# eEvo_v1_7_MP8770.net
KiCad netlist of a schematic drawn in EAGLE
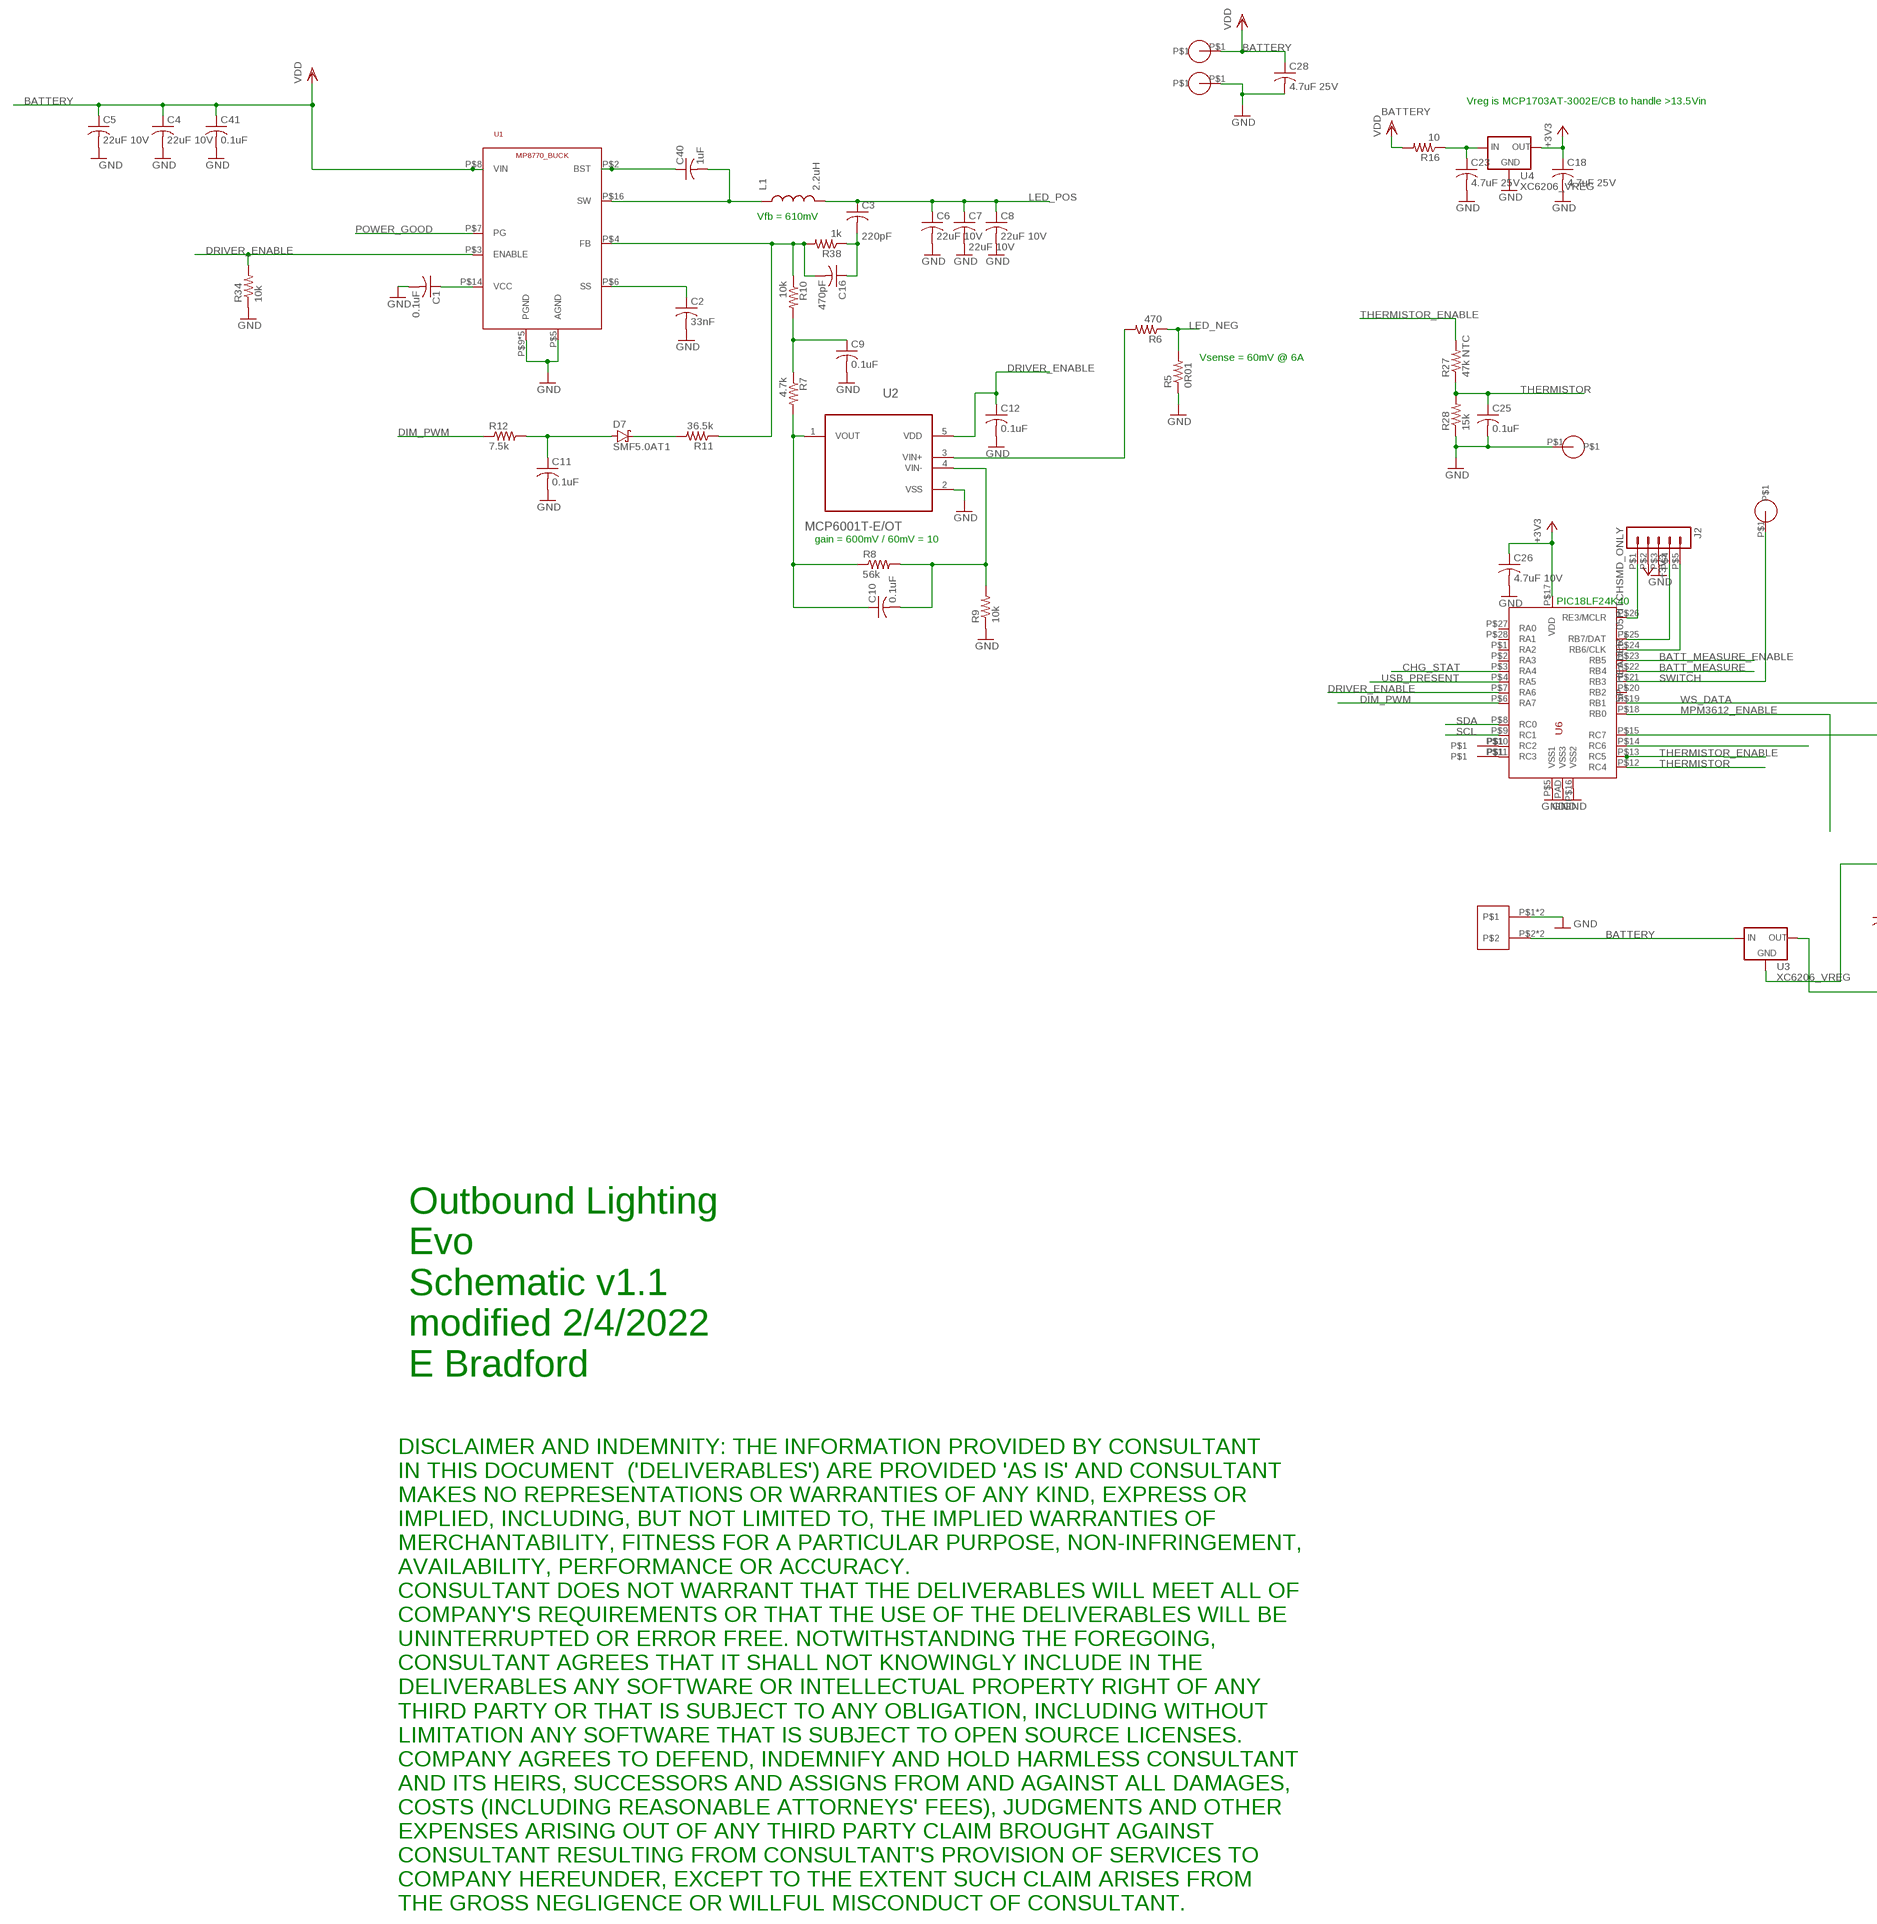
[diagram p0: schematic, sheet 1, part 1 of 2]
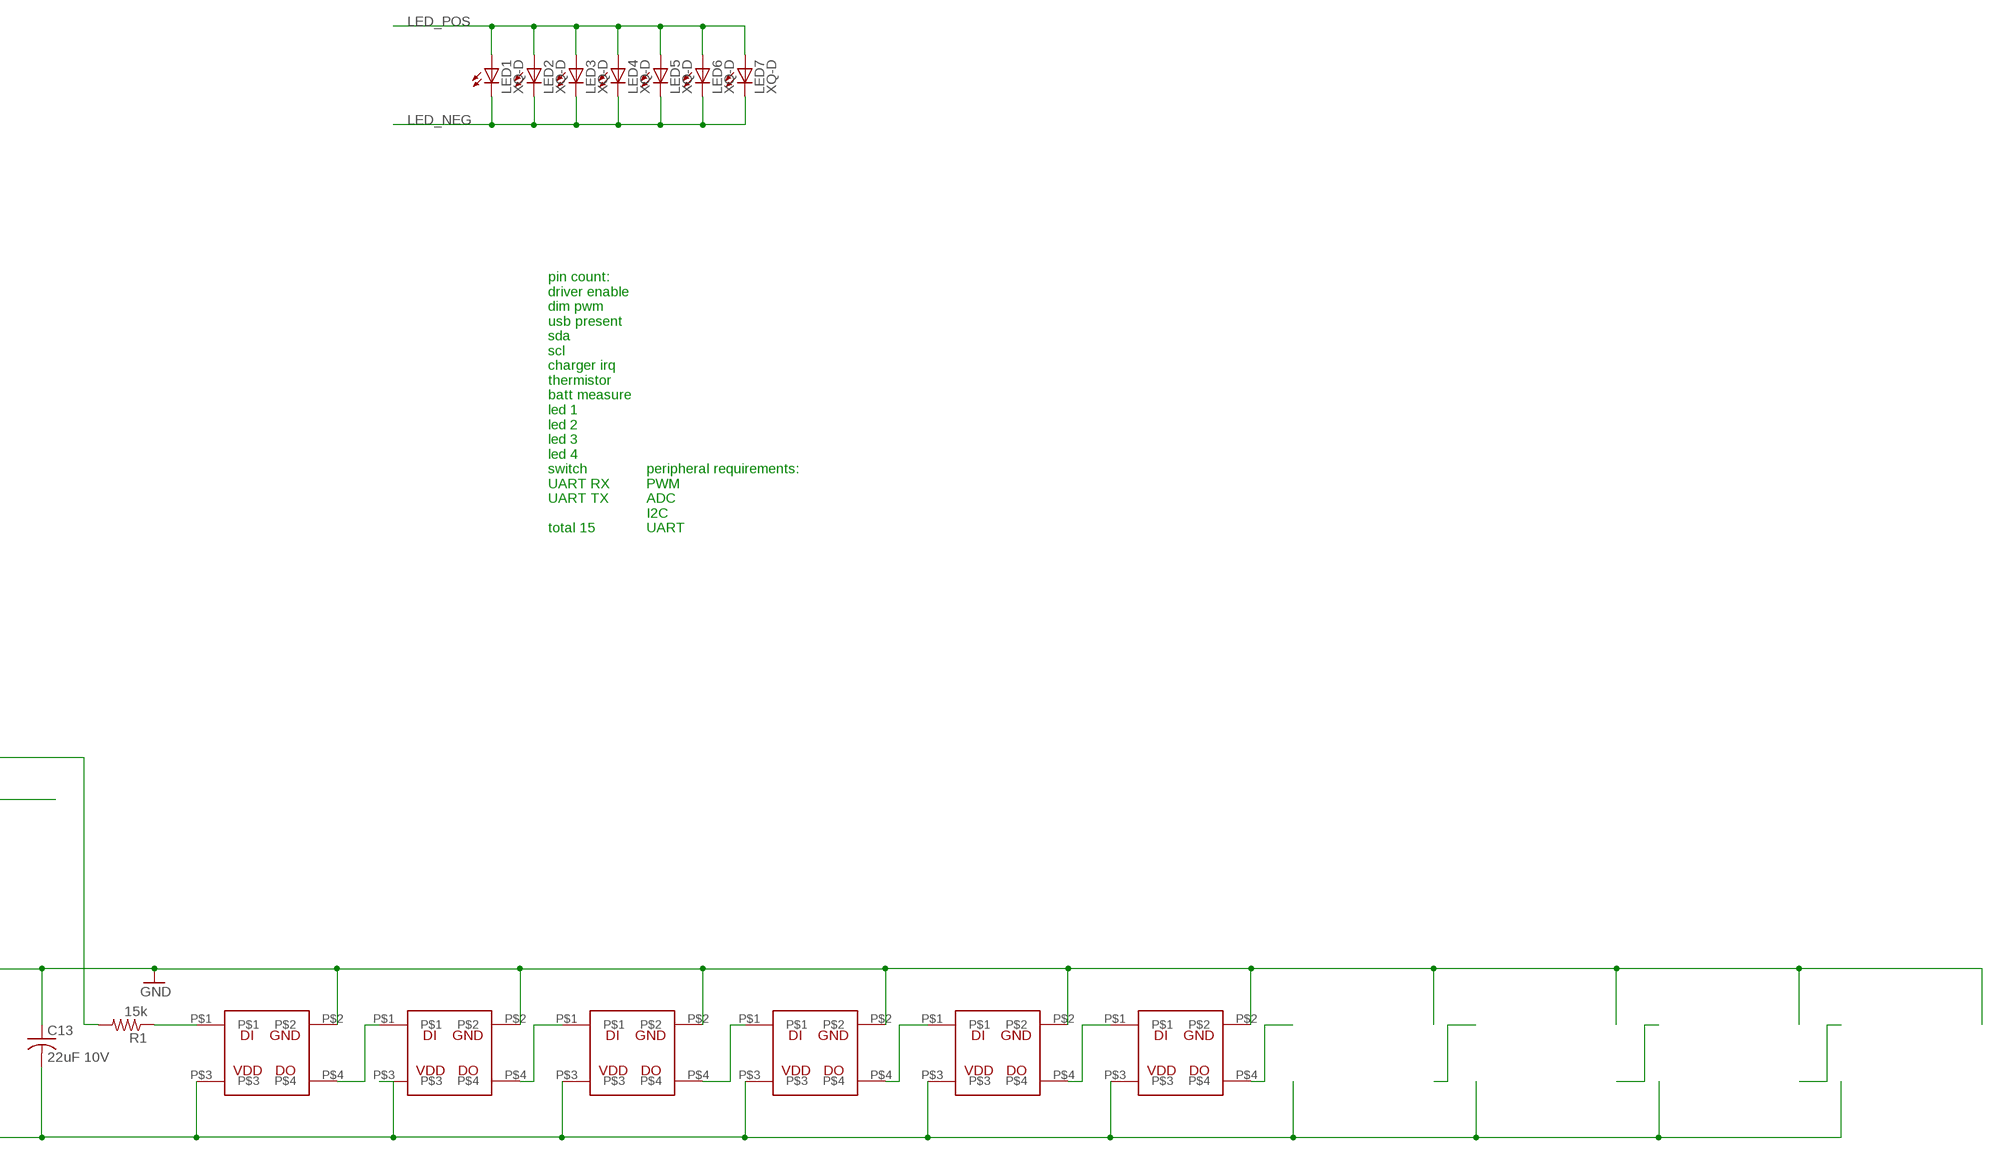
[diagram p1: schematic, sheet 1, part 2 of 2]

(export (version "E")
  (design (tool "Eeschema 10.0.6"))
  (components
    (comp (ref "C1")
      (value "0.1uF")
      (footprint "eagle-import:C0603")
      (libsource (lib "eagle-import") (part "C-USC0603"))
    )
    (comp (ref "C2")
      (value "33nF")
      (footprint "eagle-import:C0603")
      (libsource (lib "eagle-import") (part "C-USC0603"))
    )
    (comp (ref "C3")
      (value "220pF")
      (footprint "eagle-import:C0603")
      (libsource (lib "eagle-import") (part "C-USC0603"))
    )
    (comp (ref "C4")
      (value "22uF 10V")
      (footprint "eagle-import:C0603")
      (libsource (lib "eagle-import") (part "C-USC0603"))
    )
    (comp (ref "C5")
      (value "22uF 10V")
      (footprint "eagle-import:C0603")
      (libsource (lib "eagle-import") (part "C-USC0603"))
    )
    (comp (ref "C6")
      (value "22uF 10V")
      (footprint "eagle-import:C0603")
      (libsource (lib "eagle-import") (part "C-USC0603"))
    )
    (comp (ref "C7")
      (value "22uF 10V")
      (footprint "eagle-import:C0603")
      (libsource (lib "eagle-import") (part "C-USC0603"))
    )
    (comp (ref "C8")
      (value "22uF 10V")
      (footprint "eagle-import:C0603")
      (libsource (lib "eagle-import") (part "C-USC0603"))
    )
    (comp (ref "C9")
      (value "0.1uF")
      (footprint "eagle-import:C0603")
      (libsource (lib "eagle-import") (part "C-USC0603"))
    )
    (comp (ref "C10")
      (value "0.1uF")
      (footprint "eagle-import:C0603")
      (libsource (lib "eagle-import") (part "C-USC0603"))
    )
    (comp (ref "C11")
      (value "0.1uF")
      (footprint "eagle-import:C0603")
      (libsource (lib "eagle-import") (part "C-USC0603"))
    )
    (comp (ref "C12")
      (value "0.1uF")
      (footprint "eagle-import:C0603")
      (libsource (lib "eagle-import") (part "C-USC0603"))
    )
    (comp (ref "C13")
      (value "22uF 10V")
      (footprint "eagle-import:C0603")
      (libsource (lib "eagle-import") (part "C-USC0603"))
    )
    (comp (ref "C16")
      (value "470pF")
      (footprint "eagle-import:C0603")
      (libsource (lib "eagle-import") (part "C-USC0603"))
    )
    (comp (ref "C18")
      (value "4.7uF 25V")
      (footprint "eagle-import:C0603")
      (libsource (lib "eagle-import") (part "C-USC0603"))
    )
    (comp (ref "C23")
      (value "4.7uF 25V")
      (footprint "eagle-import:C0603")
      (libsource (lib "eagle-import") (part "C-USC0603"))
    )
    (comp (ref "C25")
      (value "0.1uF")
      (footprint "eagle-import:C0603")
      (libsource (lib "eagle-import") (part "C-USC0603"))
    )
    (comp (ref "C26")
      (value "4.7uF 10V")
      (footprint "eagle-import:C0603")
      (libsource (lib "eagle-import") (part "C-USC0603"))
    )
    (comp (ref "C28")
      (value "4.7uF 25V")
      (footprint "eagle-import:C0603")
      (libsource (lib "eagle-import") (part "C-USC0603"))
    )
    (comp (ref "C40")
      (value "1uF")
      (footprint "eagle-import:C0603")
      (libsource (lib "eagle-import") (part "C-USC0603"))
    )
    (comp (ref "C41")
      (value "0.1uF")
      (footprint "eagle-import:C0603")
      (libsource (lib "eagle-import") (part "C-USC0603"))
    )
    (comp (ref "D7")
      (value "SMF5.0AT1")
      (footprint "eagle-import:SOD123FL")
      (libsource (lib "eagle-import") (part "SMF5.0AT1"))
    )
    (comp (ref "J1")
      (value "CONN_2-PIN_MOLEX_PICOEZMATE")
      (footprint "eagle-import:CONN_2-PIN_MOLEX_PICOEZMATE")
      (libsource (lib "eagle-import") (part "CONN_2-PIN_MOLEX_PICOEZMATE"))
    )
    (comp (ref "J2")
      (value "5P_HEADER_.05PITCHSMD_ONLY")
      (footprint "eagle-import:5P_ICSP_SMD")
      (libsource (lib "eagle-import") (part "5P_HEADER_.05PITCHSMD_ONLY"))
    )
    (comp (ref "L1")
      (value "2.2uH")
      (footprint "eagle-import:INDUCTOR_5.7X5.2")
      (libsource (lib "eagle-import") (part "SMD_INDUCT_5.7X5.2"))
    )
    (comp (ref "LED1")
      (value "XQ-D")
      (footprint "eagle-import:XQ-D")
      (libsource (lib "eagle-import") (part "XQ-D"))
    )
    (comp (ref "LED2")
      (value "XQ-D")
      (footprint "eagle-import:XQ-D")
      (libsource (lib "eagle-import") (part "XQ-D"))
    )
    (comp (ref "LED3")
      (value "XQ-D")
      (footprint "eagle-import:XQ-D")
      (libsource (lib "eagle-import") (part "XQ-D"))
    )
    (comp (ref "LED4")
      (value "XQ-D")
      (footprint "eagle-import:XQ-D")
      (libsource (lib "eagle-import") (part "XQ-D"))
    )
    (comp (ref "LED5")
      (value "XQ-D")
      (footprint "eagle-import:XQ-D")
      (libsource (lib "eagle-import") (part "XQ-D"))
    )
    (comp (ref "LED6")
      (value "XQ-D")
      (footprint "eagle-import:XQ-D")
      (libsource (lib "eagle-import") (part "XQ-D"))
    )
    (comp (ref "LED7")
      (value "XQ-D")
      (footprint "eagle-import:XQ-D")
      (libsource (lib "eagle-import") (part "XQ-D"))
    )
    (comp (ref "R1")
      (value "15k")
      (footprint "eagle-import:R0603")
      (libsource (lib "eagle-import") (part "R-US_R0603"))
    )
    (comp (ref "R5")
      (value "0R01")
      (footprint "eagle-import:M1206")
      (libsource (lib "eagle-import") (part "R-US_M1206"))
    )
    (comp (ref "R6")
      (value "470")
      (footprint "eagle-import:R0603")
      (libsource (lib "eagle-import") (part "R-US_R0603"))
    )
    (comp (ref "R7")
      (value "4.7k")
      (footprint "eagle-import:R0603")
      (libsource (lib "eagle-import") (part "R-US_R0603"))
    )
    (comp (ref "R8")
      (value "56k")
      (footprint "eagle-import:R0603")
      (libsource (lib "eagle-import") (part "R-US_R0603"))
    )
    (comp (ref "R9")
      (value "10k")
      (footprint "eagle-import:R0603")
      (libsource (lib "eagle-import") (part "R-US_R0603"))
    )
    (comp (ref "R10")
      (value "10k")
      (footprint "eagle-import:R0603")
      (libsource (lib "eagle-import") (part "R-US_R0603"))
    )
    (comp (ref "R11")
      (value "36.5k")
      (footprint "eagle-import:R0603")
      (libsource (lib "eagle-import") (part "R-US_R0603"))
    )
    (comp (ref "R12")
      (value "7.5k")
      (footprint "eagle-import:R0603")
      (libsource (lib "eagle-import") (part "R-US_R0603"))
    )
    (comp (ref "R16")
      (value "10")
      (footprint "eagle-import:R0603")
      (libsource (lib "eagle-import") (part "R-US_R0603"))
    )
    (comp (ref "R27")
      (value "47k NTC")
      (footprint "eagle-import:R0603")
      (libsource (lib "eagle-import") (part "R-US_R0603"))
    )
    (comp (ref "R28")
      (value "15k")
      (footprint "eagle-import:R0603")
      (libsource (lib "eagle-import") (part "R-US_R0603"))
    )
    (comp (ref "R34")
      (value "10k")
      (footprint "eagle-import:R0603")
      (libsource (lib "eagle-import") (part "R-US_R0603"))
    )
    (comp (ref "R38")
      (value "1k")
      (footprint "eagle-import:R0603")
      (libsource (lib "eagle-import") (part "R-US_R0603"))
    )
    (comp (ref "RX")
      (value "WIREPAD_50MIL")
      (footprint "eagle-import:WIREPAD_50MIL")
      (libsource (lib "eagle-import") (part "WIREPAD_50MIL"))
    )
    (comp (ref "TX")
      (value "WIREPAD_50MIL")
      (footprint "eagle-import:WIREPAD_50MIL")
      (libsource (lib "eagle-import") (part "WIREPAD_50MIL"))
    )
    (comp (ref "U$2")
      (value "WS2812B-2020")
      (footprint "eagle-import:WS2812B-2020")
      (libsource (lib "eagle-import") (part "WS2812B-2020"))
    )
    (comp (ref "U$3")
      (value "WS2812B-2020")
      (footprint "eagle-import:WS2812B-2020")
      (libsource (lib "eagle-import") (part "WS2812B-2020"))
    )
    (comp (ref "U$4")
      (value "WS2812B-2020")
      (footprint "eagle-import:WS2812B-2020")
      (libsource (lib "eagle-import") (part "WS2812B-2020"))
    )
    (comp (ref "U$5")
      (value "WS2812B-2020")
      (footprint "eagle-import:WS2812B-2020")
      (libsource (lib "eagle-import") (part "WS2812B-2020"))
    )
    (comp (ref "U$6")
      (value "WS2812B-2020")
      (footprint "eagle-import:WS2812B-2020")
      (libsource (lib "eagle-import") (part "WS2812B-2020"))
    )
    (comp (ref "U$7")
      (value "WS2812B-2020")
      (footprint "eagle-import:WS2812B-2020")
      (libsource (lib "eagle-import") (part "WS2812B-2020"))
    )
    (comp (ref "U$12")
      (value "WIREPAD2X2MM_SQ")
      (footprint "eagle-import:PAD_2X2")
      (libsource (lib "eagle-import") (part "WIREPAD2X2MM_SQ"))
    )
    (comp (ref "U$13")
      (value "WIREPAD2X2MM_SQ")
      (footprint "eagle-import:PAD_2X2")
      (libsource (lib "eagle-import") (part "WIREPAD2X2MM_SQ"))
    )
    (comp (ref "U$14")
      (value "WIREPAD2X2MM_SQ")
      (footprint "eagle-import:PAD_2X2")
      (libsource (lib "eagle-import") (part "WIREPAD2X2MM_SQ"))
    )
    (comp (ref "U$15")
      (value "WIREPAD2X2MM_SQ")
      (footprint "eagle-import:PAD_2X2")
      (libsource (lib "eagle-import") (part "WIREPAD2X2MM_SQ"))
    )
    (comp (ref "U1")
      (value "MP8770_BUCK")
      (footprint "eagle-import:MP8770_BUCK")
      (libsource (lib "eagle-import") (part "MP8770_BUCK"))
    )
    (comp (ref "U2")
      (value "MCP6001T-E/OT")
      (footprint "eagle-import:SOT95P270X145-5N")
      (libsource (lib "eagle-import") (part "MCP6001T-E/OT"))
    )
    (comp (ref "U3")
      (value "XC6206_VREG")
      (footprint "eagle-import:SOT-23")
      (libsource (lib "eagle-import") (part "XC6206_VREG"))
    )
    (comp (ref "U4")
      (value "XC6206_VREG")
      (footprint "eagle-import:SOT-23")
      (libsource (lib "eagle-import") (part "XC6206_VREG"))
    )
    (comp (ref "U6")
      (value "PIC18F25K40UQFN_4X4")
      (footprint "eagle-import:UQFN-28_4X4")
      (libsource (lib "eagle-import") (part "PIC18F26K40UQFN_4X4"))
    )
  )
  (nets
    (net (code "1") (name "+3V3") (class "Default")
      (node (ref "C18") (pin "1") (pinfunction "1_1") (pintype "passive"))
      (node (ref "C26") (pin "1") (pinfunction "1_1") (pintype "passive"))
      (node (ref "J2") (pin "P$2") (pinfunction "2_P$2") (pintype "passive"))
      (node (ref "U4") (pin "2") (pinfunction "OUT_2") (pintype "passive"))
      (node (ref "U6") (pin "P$17") (pinfunction "VDD_P$17") (pintype "bidirectional"))
    )
    (net (code "2") (name "/BATT_MEASURE") (class "Default")
      (node (ref "U6") (pin "P$22") (pinfunction "RB4_P$22") (pintype "bidirectional"))
    )
    (net (code "3") (name "/BATT_MEASURE_ENABLE") (class "Default")
      (node (ref "U6") (pin "P$23") (pinfunction "RB5_P$23") (pintype "bidirectional"))
    )
    (net (code "4") (name "/CHG_STAT") (class "Default")
      (node (ref "U6") (pin "P$3") (pinfunction "RA4_P$3") (pintype "bidirectional"))
    )
    (net (code "5") (name "/DIM_PWM") (class "Default")
      (node (ref "R12") (pin "1") (pinfunction "1_1") (pintype "passive"))
      (node (ref "U6") (pin "P$6") (pinfunction "RA7_P$6") (pintype "bidirectional"))
    )
    (net (code "6") (name "/DRIVER_ENABLE") (class "Default")
      (node (ref "C12") (pin "1") (pinfunction "1_1") (pintype "passive"))
      (node (ref "R34") (pin "2") (pinfunction "2_2") (pintype "passive"))
      (node (ref "U1") (pin "P$3") (pinfunction "ENABLE_P$3") (pintype "bidirectional"))
      (node (ref "U2") (pin "5") (pinfunction "VDD_5") (pintype "power_in"))
      (node (ref "U6") (pin "P$7") (pinfunction "RA6_P$7") (pintype "bidirectional"))
    )
    (net (code "7") (name "/LED_NEG") (class "Default")
      (node (ref "LED1") (pin "2") (pinfunction "C_2") (pintype "passive"))
      (node (ref "LED2") (pin "2") (pinfunction "C_2") (pintype "passive"))
      (node (ref "LED3") (pin "2") (pinfunction "C_2") (pintype "passive"))
      (node (ref "LED4") (pin "2") (pinfunction "C_2") (pintype "passive"))
      (node (ref "LED5") (pin "2") (pinfunction "C_2") (pintype "passive"))
      (node (ref "LED6") (pin "2") (pinfunction "C_2") (pintype "passive"))
      (node (ref "LED7") (pin "2") (pinfunction "C_2") (pintype "passive"))
      (node (ref "R5") (pin "2") (pinfunction "2_2") (pintype "passive"))
      (node (ref "R6") (pin "1") (pinfunction "1_1") (pintype "passive"))
    )
    (net (code "8") (name "/LED_POS") (class "Default")
      (node (ref "C3") (pin "1") (pinfunction "1_1") (pintype "passive"))
      (node (ref "C6") (pin "1") (pinfunction "1_1") (pintype "passive"))
      (node (ref "C7") (pin "1") (pinfunction "1_1") (pintype "passive"))
      (node (ref "C8") (pin "1") (pinfunction "1_1") (pintype "passive"))
      (node (ref "L1") (pin "P$2") (pinfunction "2_P$2") (pintype "passive"))
      (node (ref "LED1") (pin "1") (pinfunction "A_1") (pintype "passive"))
      (node (ref "LED2") (pin "1") (pinfunction "A_1") (pintype "passive"))
      (node (ref "LED3") (pin "1") (pinfunction "A_1") (pintype "passive"))
      (node (ref "LED4") (pin "1") (pinfunction "A_1") (pintype "passive"))
      (node (ref "LED5") (pin "1") (pinfunction "A_1") (pintype "passive"))
      (node (ref "LED6") (pin "1") (pinfunction "A_1") (pintype "passive"))
      (node (ref "LED7") (pin "1") (pinfunction "A_1") (pintype "passive"))
    )
    (net (code "9") (name "/MPM3612_ENABLE") (class "Default")
      (node (ref "U6") (pin "P$18") (pinfunction "RB0_P$18") (pintype "bidirectional"))
    )
    (net (code "10") (name "/POWER_GOOD") (class "Default")
      (node (ref "U1") (pin "P$7") (pinfunction "PG_P$7") (pintype "bidirectional"))
    )
    (net (code "11") (name "/SCL") (class "Default")
      (node (ref "U6") (pin "P$9") (pinfunction "RC1_P$9") (pintype "bidirectional"))
    )
    (net (code "12") (name "/SDA") (class "Default")
      (node (ref "U6") (pin "P$8") (pinfunction "RC0_P$8") (pintype "bidirectional"))
    )
    (net (code "13") (name "/SWITCH") (class "Default")
      (node (ref "U$12") (pin "P$1") (pinfunction "P$1_P$1") (pintype "bidirectional"))
      (node (ref "U6") (pin "P$21") (pinfunction "RB3_P$21") (pintype "bidirectional"))
    )
    (net (code "14") (name "/THERMISTOR") (class "Default")
      (node (ref "C25") (pin "1") (pinfunction "1_1") (pintype "passive"))
      (node (ref "R27") (pin "1") (pinfunction "1_1") (pintype "passive"))
      (node (ref "R28") (pin "2") (pinfunction "2_2") (pintype "passive"))
      (node (ref "U6") (pin "P$12") (pinfunction "RC4_P$12") (pintype "bidirectional"))
    )
    (net (code "15") (name "/THERMISTOR_ENABLE") (class "Default")
      (node (ref "R27") (pin "2") (pinfunction "2_2") (pintype "passive"))
      (node (ref "U6") (pin "P$13") (pinfunction "RC5_P$13") (pintype "bidirectional"))
    )
    (net (code "16") (name "/USB_PRESENT") (class "Default")
      (node (ref "U6") (pin "P$4") (pinfunction "RA5_P$4") (pintype "bidirectional"))
    )
    (net (code "17") (name "/WS_DATA") (class "Default")
      (node (ref "R1") (pin "2") (pinfunction "2_2") (pintype "passive"))
      (node (ref "U6") (pin "P$19") (pinfunction "RB1_P$19") (pintype "bidirectional"))
    )
    (net (code "18") (name "GND") (class "Default")
      (node (ref "C1") (pin "2") (pinfunction "2_2") (pintype "passive"))
      (node (ref "C11") (pin "2") (pinfunction "2_2") (pintype "passive"))
      (node (ref "C12") (pin "2") (pinfunction "2_2") (pintype "passive"))
      (node (ref "C13") (pin "1") (pinfunction "1_1") (pintype "passive"))
      (node (ref "C18") (pin "2") (pinfunction "2_2") (pintype "passive"))
      (node (ref "C2") (pin "2") (pinfunction "2_2") (pintype "passive"))
      (node (ref "C23") (pin "2") (pinfunction "2_2") (pintype "passive"))
      (node (ref "C25") (pin "2") (pinfunction "2_2") (pintype "passive"))
      (node (ref "C26") (pin "2") (pinfunction "2_2") (pintype "passive"))
      (node (ref "C28") (pin "2") (pinfunction "2_2") (pintype "passive"))
      (node (ref "C4") (pin "2") (pinfunction "2_2") (pintype "passive"))
      (node (ref "C41") (pin "2") (pinfunction "2_2") (pintype "passive"))
      (node (ref "C5") (pin "2") (pinfunction "2_2") (pintype "passive"))
      (node (ref "C6") (pin "2") (pinfunction "2_2") (pintype "passive"))
      (node (ref "C7") (pin "2") (pinfunction "2_2") (pintype "passive"))
      (node (ref "C8") (pin "2") (pinfunction "2_2") (pintype "passive"))
      (node (ref "C9") (pin "2") (pinfunction "2_2") (pintype "passive"))
      (node (ref "J1") (pin "P$1") (pinfunction "P$1_P$1") (pintype "bidirectional"))
      (node (ref "J1") (pin "P$4") (pinfunction "P$1_P$4") (pintype "bidirectional"))
      (node (ref "J2") (pin "P$3") (pinfunction "3_P$3") (pintype "passive"))
      (node (ref "R28") (pin "1") (pinfunction "1_1") (pintype "passive"))
      (node (ref "R34") (pin "1") (pinfunction "1_1") (pintype "passive"))
      (node (ref "R5") (pin "1") (pinfunction "1_1") (pintype "passive"))
      (node (ref "R9") (pin "1") (pinfunction "1_1") (pintype "passive"))
      (node (ref "U$13") (pin "P$1") (pinfunction "P$1_P$1") (pintype "bidirectional"))
      (node (ref "U$15") (pin "P$1") (pinfunction "P$1_P$1") (pintype "bidirectional"))
      (node (ref "U$2") (pin "P$2") (pinfunction "P$2_P$2") (pintype "bidirectional"))
      (node (ref "U$3") (pin "P$2") (pinfunction "P$2_P$2") (pintype "bidirectional"))
      (node (ref "U$4") (pin "P$2") (pinfunction "P$2_P$2") (pintype "bidirectional"))
      (node (ref "U$5") (pin "P$2") (pinfunction "P$2_P$2") (pintype "bidirectional"))
      (node (ref "U$6") (pin "P$2") (pinfunction "P$2_P$2") (pintype "bidirectional"))
      (node (ref "U$7") (pin "P$2") (pinfunction "P$2_P$2") (pintype "bidirectional"))
      (node (ref "U1") (pin "P$10") (pinfunction "PGND_P$10") (pintype "bidirectional"))
      (node (ref "U1") (pin "P$11") (pinfunction "PGND_P$11") (pintype "bidirectional"))
      (node (ref "U1") (pin "P$12") (pinfunction "PGND_P$12") (pintype "bidirectional"))
      (node (ref "U1") (pin "P$13") (pinfunction "PGND_P$13") (pintype "bidirectional"))
      (node (ref "U1") (pin "P$5") (pinfunction "AGND_P$5") (pintype "bidirectional"))
      (node (ref "U1") (pin "P$9") (pinfunction "PGND_P$9") (pintype "bidirectional"))
      (node (ref "U2") (pin "2") (pinfunction "VSS_2") (pintype "passive"))
      (node (ref "U3") (pin "1") (pinfunction "GND_1") (pintype "input"))
      (node (ref "U4") (pin "1") (pinfunction "GND_1") (pintype "input"))
      (node (ref "U6") (pin "P$16") (pinfunction "VSS2_P$16") (pintype "bidirectional"))
      (node (ref "U6") (pin "P$5") (pinfunction "VSS1_P$5") (pintype "bidirectional"))
      (node (ref "U6") (pin "PAD") (pinfunction "VSS3_PAD") (pintype "bidirectional"))
    )
    (net (code "19") (name "Net-(C9-Pad1)") (class "Default")
      (node (ref "C9") (pin "1") (pinfunction "1_1") (pintype "passive"))
      (node (ref "R10") (pin "2") (pinfunction "2_2") (pintype "passive"))
      (node (ref "R7") (pin "1") (pinfunction "1_1") (pintype "passive"))
    )
    (net (code "20") (name "Net-(C11-Pad1)") (class "Default")
      (node (ref "C11") (pin "1") (pinfunction "1_1") (pintype "passive"))
      (node (ref "D7") (pin "A") (pinfunction "A_A") (pintype "passive"))
      (node (ref "R12") (pin "2") (pinfunction "2_2") (pintype "passive"))
    )
    (net (code "21") (name "Net-(C16-Pad1)") (class "Default")
      (node (ref "C16") (pin "1") (pinfunction "1_1") (pintype "passive"))
      (node (ref "C3") (pin "2") (pinfunction "2_2") (pintype "passive"))
      (node (ref "R38") (pin "1") (pinfunction "1_1") (pintype "passive"))
    )
    (net (code "22") (name "Net-(D7-PadC)") (class "Default")
      (node (ref "D7") (pin "C") (pinfunction "C_C") (pintype "passive"))
      (node (ref "R11") (pin "2") (pinfunction "2_2") (pintype "passive"))
    )
    (net (code "23") (name "Net-(J2-1)") (class "Default")
      (node (ref "J2") (pin "P$1") (pinfunction "1_P$1") (pintype "passive"))
      (node (ref "U6") (pin "P$26") (pinfunction "RE3/MCLR_P$26") (pintype "bidirectional"))
    )
    (net (code "24") (name "Net-(J2-4)") (class "Default")
      (node (ref "J2") (pin "P$4") (pinfunction "4_P$4") (pintype "passive"))
      (node (ref "U6") (pin "P$25") (pinfunction "RB7/DAT_P$25") (pintype "bidirectional"))
    )
    (net (code "25") (name "Net-(J2-5)") (class "Default")
      (node (ref "J2") (pin "P$5") (pinfunction "5_P$5") (pintype "passive"))
      (node (ref "U6") (pin "P$24") (pinfunction "RB6/CLK_P$24") (pintype "bidirectional"))
    )
    (net (code "26") (name "Net-(L1-1)") (class "Default")
      (node (ref "C40") (pin "2") (pinfunction "2_2") (pintype "passive"))
      (node (ref "L1") (pin "P$1") (pinfunction "1_P$1") (pintype "passive"))
      (node (ref "U1") (pin "P$16") (pinfunction "SW_P$16") (pintype "bidirectional"))
    )
    (net (code "27") (name "Net-(R1-Pad1)") (class "Default")
      (node (ref "R1") (pin "1") (pinfunction "1_1") (pintype "passive"))
      (node (ref "U$2") (pin "P$1") (pinfunction "P$1_P$1") (pintype "bidirectional"))
    )
    (net (code "28") (name "Net-(U$2-PadP$4)") (class "Default")
      (node (ref "U$2") (pin "P$4") (pinfunction "P$4_P$4") (pintype "bidirectional"))
      (node (ref "U$3") (pin "P$1") (pinfunction "P$1_P$1") (pintype "bidirectional"))
    )
    (net (code "29") (name "Net-(U$3-PadP$4)") (class "Default")
      (node (ref "U$3") (pin "P$4") (pinfunction "P$4_P$4") (pintype "bidirectional"))
      (node (ref "U$4") (pin "P$1") (pinfunction "P$1_P$1") (pintype "bidirectional"))
    )
    (net (code "30") (name "Net-(U$4-PadP$4)") (class "Default")
      (node (ref "U$4") (pin "P$4") (pinfunction "P$4_P$4") (pintype "bidirectional"))
      (node (ref "U$5") (pin "P$1") (pinfunction "P$1_P$1") (pintype "bidirectional"))
    )
    (net (code "31") (name "Net-(U$5-PadP$4)") (class "Default")
      (node (ref "U$5") (pin "P$4") (pinfunction "P$4_P$4") (pintype "bidirectional"))
      (node (ref "U$6") (pin "P$1") (pinfunction "P$1_P$1") (pintype "bidirectional"))
    )
    (net (code "32") (name "Net-(U$6-PadP$4)") (class "Default")
      (node (ref "U$6") (pin "P$4") (pinfunction "P$4_P$4") (pintype "bidirectional"))
      (node (ref "U$7") (pin "P$1") (pinfunction "P$1_P$1") (pintype "bidirectional"))
    )
    (net (code "33") (name "Net-(U1-BST)") (class "Default")
      (node (ref "C40") (pin "1") (pinfunction "1_1") (pintype "passive"))
      (node (ref "U1") (pin "P$2") (pinfunction "BST_P$2") (pintype "bidirectional"))
    )
    (net (code "34") (name "Net-(U1-FB)") (class "Default")
      (node (ref "C16") (pin "2") (pinfunction "2_2") (pintype "passive"))
      (node (ref "R10") (pin "1") (pinfunction "1_1") (pintype "passive"))
      (node (ref "R11") (pin "1") (pinfunction "1_1") (pintype "passive"))
      (node (ref "R38") (pin "2") (pinfunction "2_2") (pintype "passive"))
      (node (ref "U1") (pin "P$4") (pinfunction "FB_P$4") (pintype "bidirectional"))
    )
    (net (code "35") (name "Net-(U1-SS)") (class "Default")
      (node (ref "C2") (pin "1") (pinfunction "1_1") (pintype "passive"))
      (node (ref "U1") (pin "P$6") (pinfunction "SS_P$6") (pintype "bidirectional"))
    )
    (net (code "36") (name "Net-(U1-VCC)") (class "Default")
      (node (ref "C1") (pin "1") (pinfunction "1_1") (pintype "passive"))
      (node (ref "U1") (pin "P$14") (pinfunction "VCC_P$14") (pintype "bidirectional"))
    )
    (net (code "37") (name "Net-(U2-VIN+)") (class "Default")
      (node (ref "R6") (pin "2") (pinfunction "2_2") (pintype "passive"))
      (node (ref "U2") (pin "3") (pinfunction "VIN+_3") (pintype "input"))
    )
    (net (code "38") (name "Net-(U2-VIN-)") (class "Default")
      (node (ref "C10") (pin "2") (pinfunction "2_2") (pintype "passive"))
      (node (ref "R8") (pin "2") (pinfunction "2_2") (pintype "passive"))
      (node (ref "R9") (pin "2") (pinfunction "2_2") (pintype "passive"))
      (node (ref "U2") (pin "4") (pinfunction "VIN-_4") (pintype "input"))
    )
    (net (code "39") (name "Net-(U2-VOUT)") (class "Default")
      (node (ref "C10") (pin "1") (pinfunction "1_1") (pintype "passive"))
      (node (ref "R7") (pin "2") (pinfunction "2_2") (pintype "passive"))
      (node (ref "R8") (pin "1") (pinfunction "1_1") (pintype "passive"))
      (node (ref "U2") (pin "1") (pinfunction "VOUT_1") (pintype "output"))
    )
    (net (code "40") (name "Net-(U3-OUT)") (class "Default")
      (node (ref "C13") (pin "2") (pinfunction "2_2") (pintype "passive"))
      (node (ref "U$2") (pin "P$3") (pinfunction "P$3_P$3") (pintype "bidirectional"))
      (node (ref "U$3") (pin "P$3") (pinfunction "P$3_P$3") (pintype "bidirectional"))
      (node (ref "U$4") (pin "P$3") (pinfunction "P$3_P$3") (pintype "bidirectional"))
      (node (ref "U$5") (pin "P$3") (pinfunction "P$3_P$3") (pintype "bidirectional"))
      (node (ref "U$6") (pin "P$3") (pinfunction "P$3_P$3") (pintype "bidirectional"))
      (node (ref "U$7") (pin "P$3") (pinfunction "P$3_P$3") (pintype "bidirectional"))
      (node (ref "U3") (pin "2") (pinfunction "OUT_2") (pintype "passive"))
    )
    (net (code "41") (name "Net-(U4-IN)") (class "Default")
      (node (ref "C23") (pin "1") (pinfunction "1_1") (pintype "passive"))
      (node (ref "R16") (pin "1") (pinfunction "1_1") (pintype "passive"))
      (node (ref "U4") (pin "3") (pinfunction "IN_3") (pintype "input"))
    )
    (net (code "42") (name "Net-(U6-RC2)") (class "Default")
      (node (ref "TX") (pin "P$1") (pinfunction "P$1_P$1") (pintype "bidirectional"))
      (node (ref "U6") (pin "P$10") (pinfunction "RC2_P$10") (pintype "bidirectional"))
    )
    (net (code "43") (name "Net-(U6-RC3)") (class "Default")
      (node (ref "RX") (pin "P$1") (pinfunction "P$1_P$1") (pintype "bidirectional"))
      (node (ref "U6") (pin "P$11") (pinfunction "RC3_P$11") (pintype "bidirectional"))
    )
    (net (code "44") (name "VDD") (class "Default")
      (node (ref "C28") (pin "1") (pinfunction "1_1") (pintype "passive"))
      (node (ref "C4") (pin "1") (pinfunction "1_1") (pintype "passive"))
      (node (ref "C41") (pin "1") (pinfunction "1_1") (pintype "passive"))
      (node (ref "C5") (pin "1") (pinfunction "1_1") (pintype "passive"))
      (node (ref "J1") (pin "P$2") (pinfunction "P$2_P$2") (pintype "bidirectional"))
      (node (ref "J1") (pin "P$3") (pinfunction "P$2_P$3") (pintype "bidirectional"))
      (node (ref "R16") (pin "2") (pinfunction "2_2") (pintype "passive"))
      (node (ref "U$14") (pin "P$1") (pinfunction "P$1_P$1") (pintype "bidirectional"))
      (node (ref "U1") (pin "P$8") (pinfunction "VIN_P$8") (pintype "bidirectional"))
      (node (ref "U3") (pin "3") (pinfunction "IN_3") (pintype "input"))
    )
    (net (code "45") (name "unconnected-(U$7-PadP$4)") (class "Default")
      (node (ref "U$7") (pin "P$4") (pinfunction "P$4_P$4") (pintype "bidirectional"))
    )
    (net (code "46") (name "unconnected-(U6-RA0-PadP$27)") (class "Default")
      (node (ref "U6") (pin "P$27") (pinfunction "RA0_P$27") (pintype "bidirectional"))
    )
    (net (code "47") (name "unconnected-(U6-RA1-PadP$28)") (class "Default")
      (node (ref "U6") (pin "P$28") (pinfunction "RA1_P$28") (pintype "bidirectional"))
    )
    (net (code "48") (name "unconnected-(U6-RA2-PadP$1)") (class "Default")
      (node (ref "U6") (pin "P$1") (pinfunction "RA2_P$1") (pintype "bidirectional"))
    )
    (net (code "49") (name "unconnected-(U6-RA3-PadP$2)") (class "Default")
      (node (ref "U6") (pin "P$2") (pinfunction "RA3_P$2") (pintype "bidirectional"))
    )
    (net (code "50") (name "unconnected-(U6-RB2-PadP$20)") (class "Default")
      (node (ref "U6") (pin "P$20") (pinfunction "RB2_P$20") (pintype "bidirectional"))
    )
    (net (code "51") (name "unconnected-(U6-RC6-PadP$14)") (class "Default")
      (node (ref "U6") (pin "P$14") (pinfunction "RC6_P$14") (pintype "bidirectional"))
    )
    (net (code "52") (name "unconnected-(U6-RC7-PadP$15)") (class "Default")
      (node (ref "U6") (pin "P$15") (pinfunction "RC7_P$15") (pintype "bidirectional"))
    )
  )
)
